# BS170.net
KiCad netlist of a schematic drawn in EAGLE
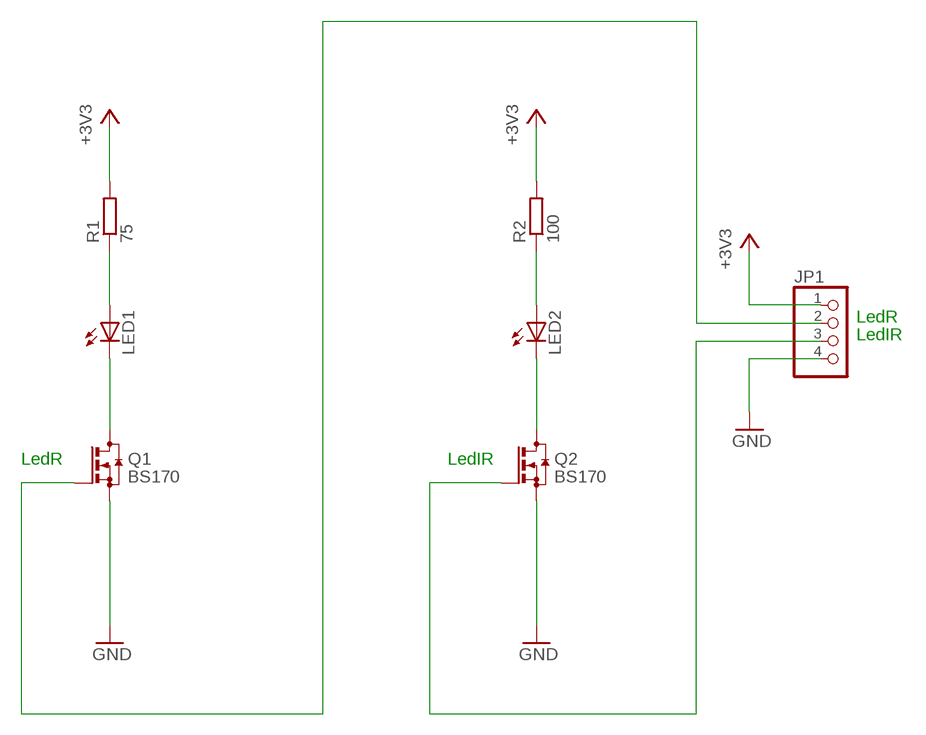
[diagram p0: schematic, sheet 1]

(export (version "E")
  (design (tool "Eeschema 10.0.6"))
  (components
    (comp (ref "JP1")
      (value "PINHD-1X4")
      (footprint "eagle-import:1X04")
      (libsource (lib "eagle-import") (part "PINHD-1X4"))
    )
    (comp (ref "LED1")
      (value "LED5MM")
      (footprint "eagle-import:LED5MM")
      (libsource (lib "eagle-import") (part "LED5MM"))
    )
    (comp (ref "LED2")
      (value "LED5MM")
      (footprint "eagle-import:LED5MM")
      (libsource (lib "eagle-import") (part "LED5MM"))
    )
    (comp (ref "Q1")
      (value "BS170")
      (footprint "eagle-import:SOT23")
      (libsource (lib "eagle-import") (part "BSS123"))
    )
    (comp (ref "Q2")
      (value "BS170")
      (footprint "eagle-import:SOT23")
      (libsource (lib "eagle-import") (part "BSS123"))
    )
    (comp (ref "R1")
      (value "75")
      (footprint "eagle-import:0207_10")
      (libsource (lib "eagle-import") (part "R-EU_0207/10"))
    )
    (comp (ref "R2")
      (value "100")
      (footprint "eagle-import:0207_10")
      (libsource (lib "eagle-import") (part "R-EU_0207/10"))
    )
  )
  (nets
    (net (code "1") (name "+3V3") (class "Default")
      (node (ref "JP1") (pin "1") (pinfunction "1_1") (pintype "passive"))
      (node (ref "R1") (pin "2") (pinfunction "2_2") (pintype "passive"))
      (node (ref "R2") (pin "2") (pinfunction "2_2") (pintype "passive"))
    )
    (net (code "2") (name "GND") (class "Default")
      (node (ref "JP1") (pin "4") (pinfunction "4_4") (pintype "passive"))
      (node (ref "Q1") (pin "2") (pinfunction "S_2") (pintype "passive"))
      (node (ref "Q2") (pin "2") (pinfunction "S_2") (pintype "passive"))
    )
    (net (code "3") (name "Net-(LED1-C)") (class "Default")
      (node (ref "LED1") (pin "K") (pinfunction "C_K") (pintype "passive"))
      (node (ref "Q1") (pin "3") (pinfunction "D_3") (pintype "passive"))
    )
    (net (code "4") (name "Net-(LED1-PadA)") (class "Default")
      (node (ref "LED1") (pin "A") (pinfunction "A_A") (pintype "passive"))
      (node (ref "R1") (pin "1") (pinfunction "1_1") (pintype "passive"))
    )
    (net (code "5") (name "Net-(LED2-C)") (class "Default")
      (node (ref "LED2") (pin "K") (pinfunction "C_K") (pintype "passive"))
      (node (ref "Q2") (pin "3") (pinfunction "D_3") (pintype "passive"))
    )
    (net (code "6") (name "Net-(LED2-PadA)") (class "Default")
      (node (ref "LED2") (pin "A") (pinfunction "A_A") (pintype "passive"))
      (node (ref "R2") (pin "1") (pinfunction "1_1") (pintype "passive"))
    )
    (net (code "7") (name "Net-(Q1-G)") (class "Default")
      (node (ref "JP1") (pin "2") (pinfunction "2_2") (pintype "passive"))
      (node (ref "Q1") (pin "1") (pinfunction "G_1") (pintype "passive"))
    )
    (net (code "8") (name "Net-(Q2-G)") (class "Default")
      (node (ref "JP1") (pin "3") (pinfunction "3_3") (pintype "passive"))
      (node (ref "Q2") (pin "1") (pinfunction "G_1") (pintype "passive"))
    )
  )
)
